# in32.net
KiCad netlist of a schematic drawn in EAGLE
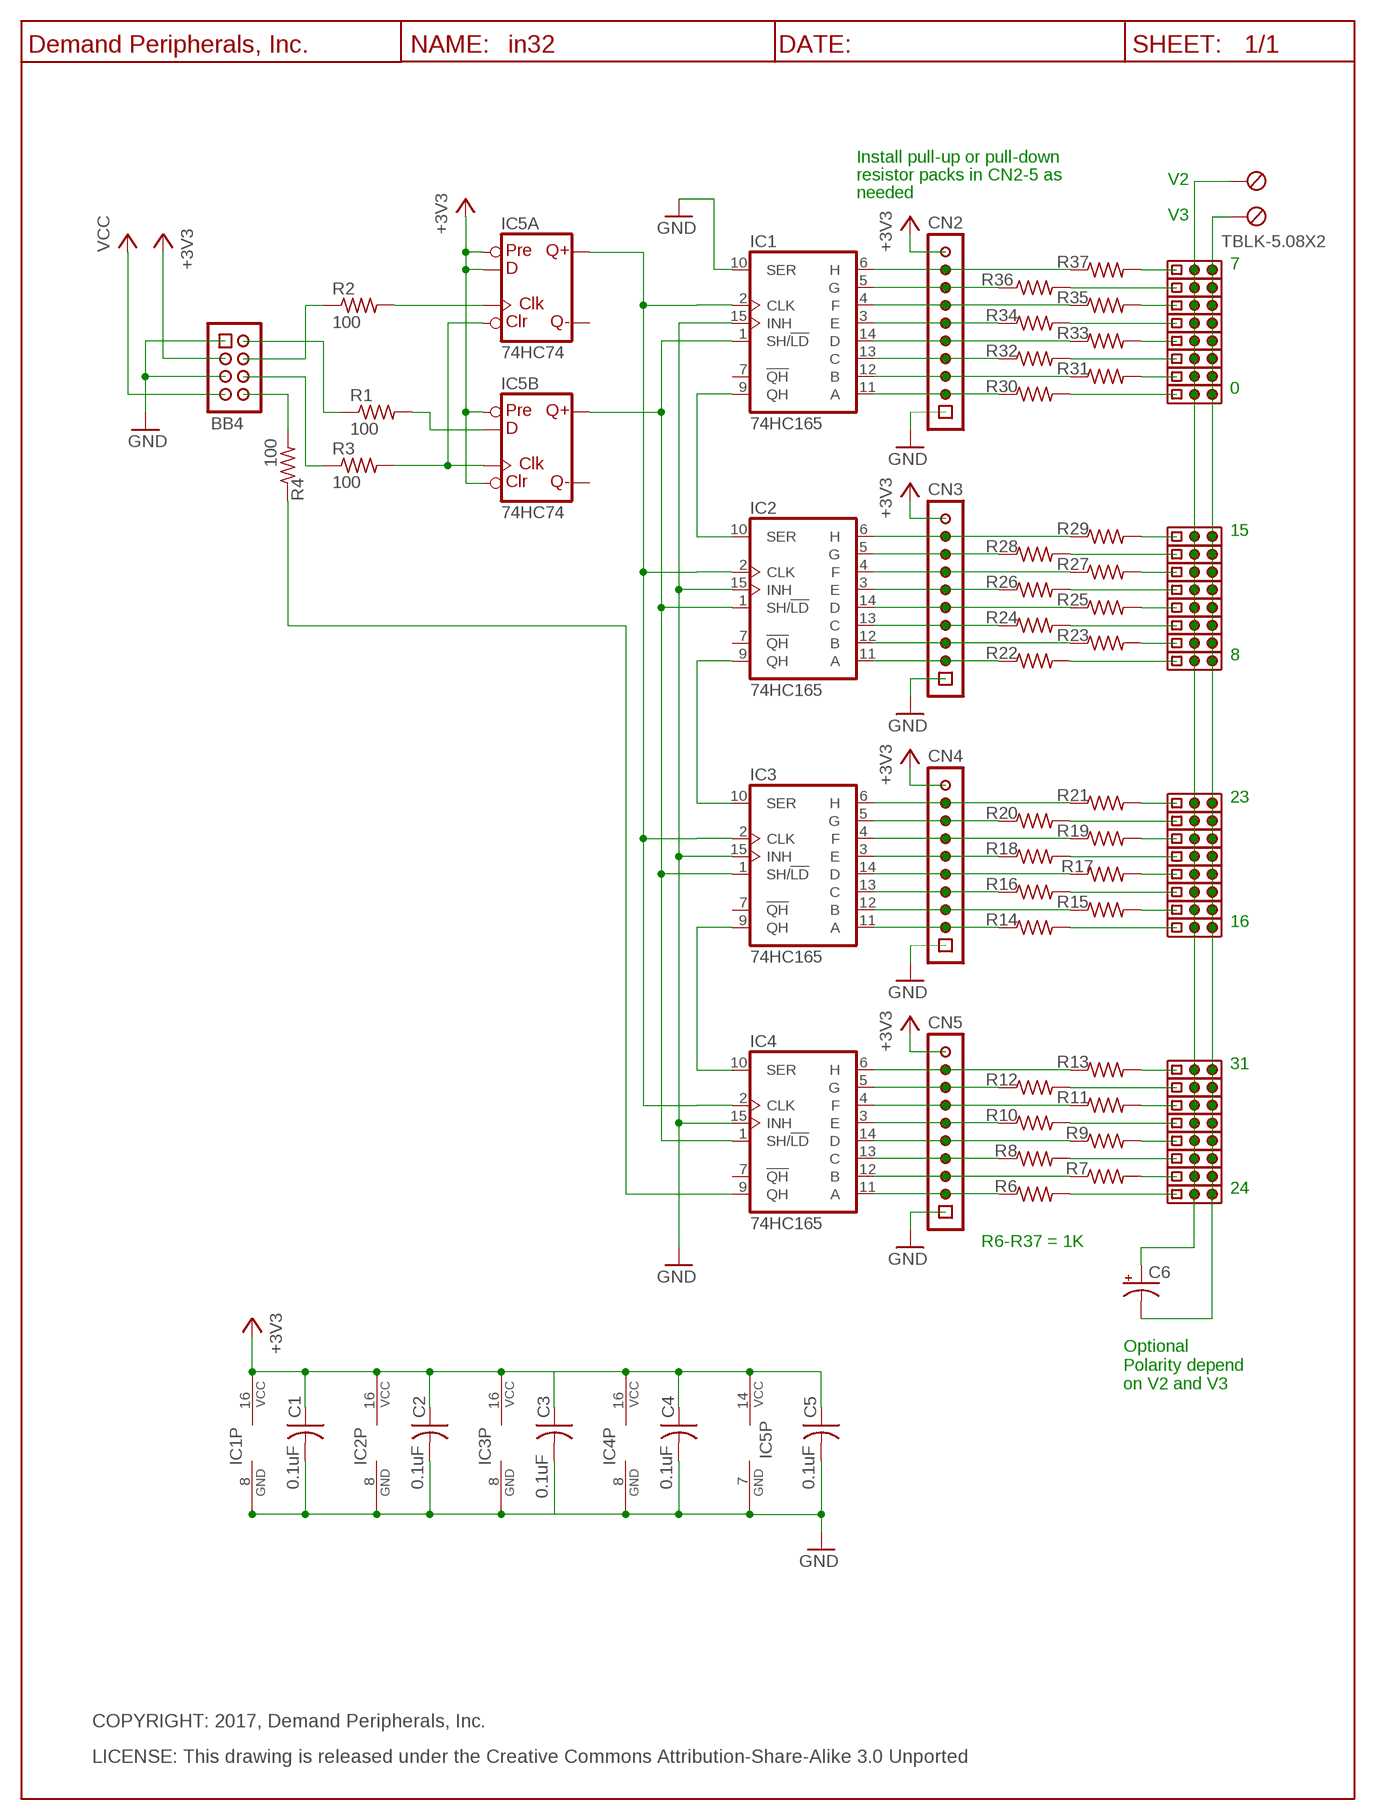
[diagram p0: schematic, sheet 1]

(export (version "E")
  (design (tool "Eeschema 10.0.6"))
  (components
    (comp (ref "BB4")
      (value "Keyed_Pin_Header_4x2(0.1\"x0.1\")")
      (footprint "eagle-import:HDR-4X2")
      (libsource (lib "eagle-import") (part "HDR-4X2-SHR"))
    )
    (comp (ref "C1")
      (value "0.1uF")
      (footprint "eagle-import:C0603")
      (libsource (lib "eagle-import") (part "C0.1UF_C0603"))
    )
    (comp (ref "C2")
      (value "0.1uF")
      (footprint "eagle-import:C0603")
      (libsource (lib "eagle-import") (part "C0.1UF_C0603"))
    )
    (comp (ref "C3")
      (value "0.1uF")
      (footprint "eagle-import:C0603")
      (libsource (lib "eagle-import") (part "C0.1UF_C0603"))
    )
    (comp (ref "C4")
      (value "0.1uF")
      (footprint "eagle-import:C0603")
      (libsource (lib "eagle-import") (part "C0.1UF_C0603"))
    )
    (comp (ref "C5")
      (value "0.1uF")
      (footprint "eagle-import:C0603")
      (libsource (lib "eagle-import") (part "C0.1UF_C0603"))
    )
    (comp (ref "C6")
      (value "C100UF_E3.5-10")
      (footprint "eagle-import:E3.5-10")
      (libsource (lib "eagle-import") (part "C100UF_E3.5-10"))
    )
    (comp (ref "CN1")
      (value "TBLK-5.08X2")
      (footprint "eagle-import:TBLK-5.08-X2")
      (libsource (lib "eagle-import") (part "TBLK-5.08-X2"))
    )
    (comp (ref "CN2")
      (value "HDR-10X1")
      (footprint "eagle-import:HDR-10X1")
      (libsource (lib "eagle-import") (part "HDR-10X1"))
    )
    (comp (ref "CN3")
      (value "HDR-10X1")
      (footprint "eagle-import:HDR-10X1")
      (libsource (lib "eagle-import") (part "HDR-10X1"))
    )
    (comp (ref "CN4")
      (value "HDR-10X1")
      (footprint "eagle-import:HDR-10X1")
      (libsource (lib "eagle-import") (part "HDR-10X1"))
    )
    (comp (ref "CN5")
      (value "HDR-10X1")
      (footprint "eagle-import:HDR-10X1")
      (libsource (lib "eagle-import") (part "HDR-10X1"))
    )
    (comp (ref "IC1")
      (value "74HC165")
      (footprint "eagle-import:SO16")
      (libsource (lib "eagle-import") (part "74HC165"))
    )
    (comp (ref "IC2")
      (value "74HC165")
      (footprint "eagle-import:SO16")
      (libsource (lib "eagle-import") (part "74HC165"))
    )
    (comp (ref "IC3")
      (value "74HC165")
      (footprint "eagle-import:SO16")
      (libsource (lib "eagle-import") (part "74HC165"))
    )
    (comp (ref "IC4")
      (value "74HC165")
      (footprint "eagle-import:SO16")
      (libsource (lib "eagle-import") (part "74HC165"))
    )
    (comp (ref "IC5")
      (value "74HC74")
      (footprint "eagle-import:SO14")
      (libsource (lib "eagle-import") (part "74AHC74"))
    )
    (comp (ref "R1")
      (value "100")
      (footprint "eagle-import:R0603")
      (libsource (lib "eagle-import") (part "R100_R0603"))
    )
    (comp (ref "R2")
      (value "100")
      (footprint "eagle-import:R0603")
      (libsource (lib "eagle-import") (part "R100_R0603"))
    )
    (comp (ref "R3")
      (value "100")
      (footprint "eagle-import:R0603")
      (libsource (lib "eagle-import") (part "R100_R0603"))
    )
    (comp (ref "R4")
      (value "100")
      (footprint "eagle-import:R0603")
      (libsource (lib "eagle-import") (part "R100_R0603"))
    )
    (comp (ref "R6")
      (value "R1K_R0603")
      (footprint "eagle-import:R0603")
      (libsource (lib "eagle-import") (part "R1K_R0603"))
    )
    (comp (ref "R7")
      (value "R1K_R0603")
      (footprint "eagle-import:R0603")
      (libsource (lib "eagle-import") (part "R1K_R0603"))
    )
    (comp (ref "R8")
      (value "R1K_R0603")
      (footprint "eagle-import:R0603")
      (libsource (lib "eagle-import") (part "R1K_R0603"))
    )
    (comp (ref "R9")
      (value "R1K_R0603")
      (footprint "eagle-import:R0603")
      (libsource (lib "eagle-import") (part "R1K_R0603"))
    )
    (comp (ref "R10")
      (value "R1K_R0603")
      (footprint "eagle-import:R0603")
      (libsource (lib "eagle-import") (part "R1K_R0603"))
    )
    (comp (ref "R11")
      (value "R1K_R0603")
      (footprint "eagle-import:R0603")
      (libsource (lib "eagle-import") (part "R1K_R0603"))
    )
    (comp (ref "R12")
      (value "R1K_R0603")
      (footprint "eagle-import:R0603")
      (libsource (lib "eagle-import") (part "R1K_R0603"))
    )
    (comp (ref "R13")
      (value "R1K_R0603")
      (footprint "eagle-import:R0603")
      (libsource (lib "eagle-import") (part "R1K_R0603"))
    )
    (comp (ref "R14")
      (value "R1K_R0603")
      (footprint "eagle-import:R0603")
      (libsource (lib "eagle-import") (part "R1K_R0603"))
    )
    (comp (ref "R15")
      (value "R1K_R0603")
      (footprint "eagle-import:R0603")
      (libsource (lib "eagle-import") (part "R1K_R0603"))
    )
    (comp (ref "R16")
      (value "R1K_R0603")
      (footprint "eagle-import:R0603")
      (libsource (lib "eagle-import") (part "R1K_R0603"))
    )
    (comp (ref "R17")
      (value "R1K_R0603")
      (footprint "eagle-import:R0603")
      (libsource (lib "eagle-import") (part "R1K_R0603"))
    )
    (comp (ref "R18")
      (value "R1K_R0603")
      (footprint "eagle-import:R0603")
      (libsource (lib "eagle-import") (part "R1K_R0603"))
    )
    (comp (ref "R19")
      (value "R1K_R0603")
      (footprint "eagle-import:R0603")
      (libsource (lib "eagle-import") (part "R1K_R0603"))
    )
    (comp (ref "R20")
      (value "R1K_R0603")
      (footprint "eagle-import:R0603")
      (libsource (lib "eagle-import") (part "R1K_R0603"))
    )
    (comp (ref "R21")
      (value "R1K_R0603")
      (footprint "eagle-import:R0603")
      (libsource (lib "eagle-import") (part "R1K_R0603"))
    )
    (comp (ref "R22")
      (value "R1K_R0603")
      (footprint "eagle-import:R0603")
      (libsource (lib "eagle-import") (part "R1K_R0603"))
    )
    (comp (ref "R23")
      (value "R1K_R0603")
      (footprint "eagle-import:R0603")
      (libsource (lib "eagle-import") (part "R1K_R0603"))
    )
    (comp (ref "R24")
      (value "R1K_R0603")
      (footprint "eagle-import:R0603")
      (libsource (lib "eagle-import") (part "R1K_R0603"))
    )
    (comp (ref "R25")
      (value "R1K_R0603")
      (footprint "eagle-import:R0603")
      (libsource (lib "eagle-import") (part "R1K_R0603"))
    )
    (comp (ref "R26")
      (value "R1K_R0603")
      (footprint "eagle-import:R0603")
      (libsource (lib "eagle-import") (part "R1K_R0603"))
    )
    (comp (ref "R27")
      (value "R1K_R0603")
      (footprint "eagle-import:R0603")
      (libsource (lib "eagle-import") (part "R1K_R0603"))
    )
    (comp (ref "R28")
      (value "R1K_R0603")
      (footprint "eagle-import:R0603")
      (libsource (lib "eagle-import") (part "R1K_R0603"))
    )
    (comp (ref "R29")
      (value "R1K_R0603")
      (footprint "eagle-import:R0603")
      (libsource (lib "eagle-import") (part "R1K_R0603"))
    )
    (comp (ref "R30")
      (value "R1K_R0603")
      (footprint "eagle-import:R0603")
      (libsource (lib "eagle-import") (part "R1K_R0603"))
    )
    (comp (ref "R31")
      (value "R1K_R0603")
      (footprint "eagle-import:R0603")
      (libsource (lib "eagle-import") (part "R1K_R0603"))
    )
    (comp (ref "R32")
      (value "R1K_R0603")
      (footprint "eagle-import:R0603")
      (libsource (lib "eagle-import") (part "R1K_R0603"))
    )
    (comp (ref "R33")
      (value "R1K_R0603")
      (footprint "eagle-import:R0603")
      (libsource (lib "eagle-import") (part "R1K_R0603"))
    )
    (comp (ref "R34")
      (value "R1K_R0603")
      (footprint "eagle-import:R0603")
      (libsource (lib "eagle-import") (part "R1K_R0603"))
    )
    (comp (ref "R35")
      (value "R1K_R0603")
      (footprint "eagle-import:R0603")
      (libsource (lib "eagle-import") (part "R1K_R0603"))
    )
    (comp (ref "R36")
      (value "R1K_R0603")
      (footprint "eagle-import:R0603")
      (libsource (lib "eagle-import") (part "R1K_R0603"))
    )
    (comp (ref "R37")
      (value "R1K_R0603")
      (footprint "eagle-import:R0603")
      (libsource (lib "eagle-import") (part "R1K_R0603"))
    )
    (comp (ref "U$2")
      (value "DP_FRAME_P")
      (footprint "eagle-import:P_FRAME")
      (libsource (lib "eagle-import") (part "DP_FRAME_P"))
    )
    (comp (ref "U$8")
      (value "HDR-3X1")
      (footprint "eagle-import:HDR-3X1")
      (libsource (lib "eagle-import") (part "HDR-3X1"))
    )
    (comp (ref "U$9")
      (value "HDR-3X1")
      (footprint "eagle-import:HDR-3X1")
      (libsource (lib "eagle-import") (part "HDR-3X1"))
    )
    (comp (ref "U$10")
      (value "HDR-3X1")
      (footprint "eagle-import:HDR-3X1")
      (libsource (lib "eagle-import") (part "HDR-3X1"))
    )
    (comp (ref "U$11")
      (value "HDR-3X1")
      (footprint "eagle-import:HDR-3X1")
      (libsource (lib "eagle-import") (part "HDR-3X1"))
    )
    (comp (ref "U$12")
      (value "HDR-3X1")
      (footprint "eagle-import:HDR-3X1")
      (libsource (lib "eagle-import") (part "HDR-3X1"))
    )
    (comp (ref "U$13")
      (value "HDR-3X1")
      (footprint "eagle-import:HDR-3X1")
      (libsource (lib "eagle-import") (part "HDR-3X1"))
    )
    (comp (ref "U$14")
      (value "HDR-3X1")
      (footprint "eagle-import:HDR-3X1")
      (libsource (lib "eagle-import") (part "HDR-3X1"))
    )
    (comp (ref "U$15")
      (value "HDR-3X1")
      (footprint "eagle-import:HDR-3X1")
      (libsource (lib "eagle-import") (part "HDR-3X1"))
    )
    (comp (ref "U$16")
      (value "HDR-3X1")
      (footprint "eagle-import:HDR-3X1")
      (libsource (lib "eagle-import") (part "HDR-3X1"))
    )
    (comp (ref "U$17")
      (value "HDR-3X1")
      (footprint "eagle-import:HDR-3X1")
      (libsource (lib "eagle-import") (part "HDR-3X1"))
    )
    (comp (ref "U$18")
      (value "HDR-3X1")
      (footprint "eagle-import:HDR-3X1")
      (libsource (lib "eagle-import") (part "HDR-3X1"))
    )
    (comp (ref "U$19")
      (value "HDR-3X1")
      (footprint "eagle-import:HDR-3X1")
      (libsource (lib "eagle-import") (part "HDR-3X1"))
    )
    (comp (ref "U$20")
      (value "HDR-3X1")
      (footprint "eagle-import:HDR-3X1")
      (libsource (lib "eagle-import") (part "HDR-3X1"))
    )
    (comp (ref "U$21")
      (value "HDR-3X1")
      (footprint "eagle-import:HDR-3X1")
      (libsource (lib "eagle-import") (part "HDR-3X1"))
    )
    (comp (ref "U$22")
      (value "HDR-3X1")
      (footprint "eagle-import:HDR-3X1")
      (libsource (lib "eagle-import") (part "HDR-3X1"))
    )
    (comp (ref "U$23")
      (value "HDR-3X1")
      (footprint "eagle-import:HDR-3X1")
      (libsource (lib "eagle-import") (part "HDR-3X1"))
    )
    (comp (ref "U$24")
      (value "HDR-3X1")
      (footprint "eagle-import:HDR-3X1")
      (libsource (lib "eagle-import") (part "HDR-3X1"))
    )
    (comp (ref "U$25")
      (value "HDR-3X1")
      (footprint "eagle-import:HDR-3X1")
      (libsource (lib "eagle-import") (part "HDR-3X1"))
    )
    (comp (ref "U$26")
      (value "HDR-3X1")
      (footprint "eagle-import:HDR-3X1")
      (libsource (lib "eagle-import") (part "HDR-3X1"))
    )
    (comp (ref "U$27")
      (value "HDR-3X1")
      (footprint "eagle-import:HDR-3X1")
      (libsource (lib "eagle-import") (part "HDR-3X1"))
    )
    (comp (ref "U$28")
      (value "HDR-3X1")
      (footprint "eagle-import:HDR-3X1")
      (libsource (lib "eagle-import") (part "HDR-3X1"))
    )
    (comp (ref "U$29")
      (value "HDR-3X1")
      (footprint "eagle-import:HDR-3X1")
      (libsource (lib "eagle-import") (part "HDR-3X1"))
    )
    (comp (ref "U$30")
      (value "HDR-3X1")
      (footprint "eagle-import:HDR-3X1")
      (libsource (lib "eagle-import") (part "HDR-3X1"))
    )
    (comp (ref "U$31")
      (value "HDR-3X1")
      (footprint "eagle-import:HDR-3X1")
      (libsource (lib "eagle-import") (part "HDR-3X1"))
    )
    (comp (ref "U$32")
      (value "HDR-3X1")
      (footprint "eagle-import:HDR-3X1")
      (libsource (lib "eagle-import") (part "HDR-3X1"))
    )
    (comp (ref "U$33")
      (value "HDR-3X1")
      (footprint "eagle-import:HDR-3X1")
      (libsource (lib "eagle-import") (part "HDR-3X1"))
    )
    (comp (ref "U$34")
      (value "HDR-3X1")
      (footprint "eagle-import:HDR-3X1")
      (libsource (lib "eagle-import") (part "HDR-3X1"))
    )
    (comp (ref "U$35")
      (value "HDR-3X1")
      (footprint "eagle-import:HDR-3X1")
      (libsource (lib "eagle-import") (part "HDR-3X1"))
    )
    (comp (ref "U$36")
      (value "HDR-3X1")
      (footprint "eagle-import:HDR-3X1")
      (libsource (lib "eagle-import") (part "HDR-3X1"))
    )
    (comp (ref "U$37")
      (value "HDR-3X1")
      (footprint "eagle-import:HDR-3X1")
      (libsource (lib "eagle-import") (part "HDR-3X1"))
    )
    (comp (ref "U$38")
      (value "HDR-3X1")
      (footprint "eagle-import:HDR-3X1")
      (libsource (lib "eagle-import") (part "HDR-3X1"))
    )
    (comp (ref "U$39")
      (value "HDR-3X1")
      (footprint "eagle-import:HDR-3X1")
      (libsource (lib "eagle-import") (part "HDR-3X1"))
    )
  )
  (nets
    (net (code "1") (name "+3V3") (class "Default")
      (node (ref "BB4") (pin "3") (pinfunction "3_3") (pintype "passive"))
      (node (ref "C1") (pin "1") (pinfunction "1_1") (pintype "passive"))
      (node (ref "C2") (pin "1") (pinfunction "1_1") (pintype "passive"))
      (node (ref "C3") (pin "1") (pinfunction "1_1") (pintype "passive"))
      (node (ref "C4") (pin "1") (pinfunction "1_1") (pintype "passive"))
      (node (ref "C5") (pin "1") (pinfunction "1_1") (pintype "passive"))
      (node (ref "CN2") (pin "10") (pinfunction "10_10") (pintype "passive"))
      (node (ref "CN3") (pin "10") (pinfunction "10_10") (pintype "passive"))
      (node (ref "CN4") (pin "10") (pinfunction "10_10") (pintype "passive"))
      (node (ref "CN5") (pin "10") (pinfunction "10_10") (pintype "passive"))
      (node (ref "IC1") (pin "16") (pinfunction "VCC_16") (pintype "power_in"))
      (node (ref "IC2") (pin "16") (pinfunction "VCC_16") (pintype "power_in"))
      (node (ref "IC3") (pin "16") (pinfunction "VCC_16") (pintype "power_in"))
      (node (ref "IC4") (pin "16") (pinfunction "VCC_16") (pintype "power_in"))
      (node (ref "IC5") (pin "10") (pinfunction "PRE_10") (pintype "input"))
      (node (ref "IC5") (pin "13") (pinfunction "CLR_13") (pintype "input"))
      (node (ref "IC5") (pin "14") (pinfunction "VCC_14") (pintype "power_in"))
      (node (ref "IC5") (pin "2") (pinfunction "D_2") (pintype "input"))
      (node (ref "IC5") (pin "4") (pinfunction "PRE_4") (pintype "input"))
    )
    (net (code "2") (name "GND") (class "Default")
      (node (ref "BB4") (pin "1") (pinfunction "1_1") (pintype "passive"))
      (node (ref "BB4") (pin "5") (pinfunction "5_5") (pintype "passive"))
      (node (ref "C1") (pin "2") (pinfunction "2_2") (pintype "passive"))
      (node (ref "C2") (pin "2") (pinfunction "2_2") (pintype "passive"))
      (node (ref "C3") (pin "2") (pinfunction "2_2") (pintype "passive"))
      (node (ref "C4") (pin "2") (pinfunction "2_2") (pintype "passive"))
      (node (ref "C5") (pin "2") (pinfunction "2_2") (pintype "passive"))
      (node (ref "CN2") (pin "1") (pinfunction "1_1") (pintype "passive"))
      (node (ref "CN3") (pin "1") (pinfunction "1_1") (pintype "passive"))
      (node (ref "CN4") (pin "1") (pinfunction "1_1") (pintype "passive"))
      (node (ref "CN5") (pin "1") (pinfunction "1_1") (pintype "passive"))
      (node (ref "IC1") (pin "10") (pinfunction "SER_10") (pintype "input"))
      (node (ref "IC1") (pin "15") (pinfunction "INH_15") (pintype "input"))
      (node (ref "IC1") (pin "8") (pinfunction "GND_8") (pintype "power_in"))
      (node (ref "IC2") (pin "15") (pinfunction "INH_15") (pintype "input"))
      (node (ref "IC2") (pin "8") (pinfunction "GND_8") (pintype "power_in"))
      (node (ref "IC3") (pin "15") (pinfunction "INH_15") (pintype "input"))
      (node (ref "IC3") (pin "8") (pinfunction "GND_8") (pintype "power_in"))
      (node (ref "IC4") (pin "15") (pinfunction "INH_15") (pintype "input"))
      (node (ref "IC4") (pin "8") (pinfunction "GND_8") (pintype "power_in"))
      (node (ref "IC5") (pin "7") (pinfunction "GND_7") (pintype "power_in"))
    )
    (net (code "3") (name "Net-(BB4-Pad2)") (class "Default")
      (node (ref "BB4") (pin "2") (pinfunction "2_2") (pintype "passive"))
      (node (ref "R1") (pin "1") (pinfunction "1_1") (pintype "passive"))
    )
    (net (code "4") (name "Net-(BB4-Pad4)") (class "Default")
      (node (ref "BB4") (pin "4") (pinfunction "4_4") (pintype "passive"))
      (node (ref "R2") (pin "1") (pinfunction "1_1") (pintype "passive"))
    )
    (net (code "5") (name "Net-(BB4-Pad6)") (class "Default")
      (node (ref "BB4") (pin "6") (pinfunction "6_6") (pintype "passive"))
      (node (ref "R3") (pin "1") (pinfunction "1_1") (pintype "passive"))
    )
    (net (code "6") (name "Net-(BB4-Pad8)") (class "Default")
      (node (ref "BB4") (pin "8") (pinfunction "8_8") (pintype "passive"))
      (node (ref "R4") (pin "2") (pinfunction "2_2") (pintype "passive"))
    )
    (net (code "7") (name "Net-(CN1-KL)") (class "Default")
      (node (ref "C6") (pin "+") (pinfunction "+_+") (pintype "passive"))
      (node (ref "CN1") (pin "1") (pinfunction "KL_1") (pintype "passive"))
      (node (ref "U$10") (pin "2") (pinfunction "2_2") (pintype "passive"))
      (node (ref "U$11") (pin "2") (pinfunction "2_2") (pintype "passive"))
      (node (ref "U$12") (pin "2") (pinfunction "2_2") (pintype "passive"))
      (node (ref "U$13") (pin "2") (pinfunction "2_2") (pintype "passive"))
      (node (ref "U$14") (pin "2") (pinfunction "2_2") (pintype "passive"))
      (node (ref "U$15") (pin "2") (pinfunction "2_2") (pintype "passive"))
      (node (ref "U$16") (pin "2") (pinfunction "2_2") (pintype "passive"))
      (node (ref "U$17") (pin "2") (pinfunction "2_2") (pintype "passive"))
      (node (ref "U$18") (pin "2") (pinfunction "2_2") (pintype "passive"))
      (node (ref "U$19") (pin "2") (pinfunction "2_2") (pintype "passive"))
      (node (ref "U$20") (pin "2") (pinfunction "2_2") (pintype "passive"))
      (node (ref "U$21") (pin "2") (pinfunction "2_2") (pintype "passive"))
      (node (ref "U$22") (pin "2") (pinfunction "2_2") (pintype "passive"))
      (node (ref "U$23") (pin "2") (pinfunction "2_2") (pintype "passive"))
      (node (ref "U$24") (pin "2") (pinfunction "2_2") (pintype "passive"))
      (node (ref "U$25") (pin "2") (pinfunction "2_2") (pintype "passive"))
      (node (ref "U$26") (pin "2") (pinfunction "2_2") (pintype "passive"))
      (node (ref "U$27") (pin "2") (pinfunction "2_2") (pintype "passive"))
      (node (ref "U$28") (pin "2") (pinfunction "2_2") (pintype "passive"))
      (node (ref "U$29") (pin "2") (pinfunction "2_2") (pintype "passive"))
      (node (ref "U$30") (pin "2") (pinfunction "2_2") (pintype "passive"))
      (node (ref "U$31") (pin "2") (pinfunction "2_2") (pintype "passive"))
      (node (ref "U$32") (pin "2") (pinfunction "2_2") (pintype "passive"))
      (node (ref "U$33") (pin "2") (pinfunction "2_2") (pintype "passive"))
      (node (ref "U$34") (pin "2") (pinfunction "2_2") (pintype "passive"))
      (node (ref "U$35") (pin "2") (pinfunction "2_2") (pintype "passive"))
      (node (ref "U$36") (pin "2") (pinfunction "2_2") (pintype "passive"))
      (node (ref "U$37") (pin "2") (pinfunction "2_2") (pintype "passive"))
      (node (ref "U$38") (pin "2") (pinfunction "2_2") (pintype "passive"))
      (node (ref "U$39") (pin "2") (pinfunction "2_2") (pintype "passive"))
      (node (ref "U$8") (pin "2") (pinfunction "2_2") (pintype "passive"))
      (node (ref "U$9") (pin "2") (pinfunction "2_2") (pintype "passive"))
    )
    (net (code "8") (name "Net-(CN1-KL1)") (class "Default")
      (node (ref "C6") (pin "-") (pinfunction "-_-") (pintype "passive"))
      (node (ref "CN1") (pin "2") (pinfunction "KL1_2") (pintype "passive"))
      (node (ref "U$10") (pin "3") (pinfunction "3_3") (pintype "passive"))
      (node (ref "U$11") (pin "3") (pinfunction "3_3") (pintype "passive"))
      (node (ref "U$12") (pin "3") (pinfunction "3_3") (pintype "passive"))
      (node (ref "U$13") (pin "3") (pinfunction "3_3") (pintype "passive"))
      (node (ref "U$14") (pin "3") (pinfunction "3_3") (pintype "passive"))
      (node (ref "U$15") (pin "3") (pinfunction "3_3") (pintype "passive"))
      (node (ref "U$16") (pin "3") (pinfunction "3_3") (pintype "passive"))
      (node (ref "U$17") (pin "3") (pinfunction "3_3") (pintype "passive"))
      (node (ref "U$18") (pin "3") (pinfunction "3_3") (pintype "passive"))
      (node (ref "U$19") (pin "3") (pinfunction "3_3") (pintype "passive"))
      (node (ref "U$20") (pin "3") (pinfunction "3_3") (pintype "passive"))
      (node (ref "U$21") (pin "3") (pinfunction "3_3") (pintype "passive"))
      (node (ref "U$22") (pin "3") (pinfunction "3_3") (pintype "passive"))
      (node (ref "U$23") (pin "3") (pinfunction "3_3") (pintype "passive"))
      (node (ref "U$24") (pin "3") (pinfunction "3_3") (pintype "passive"))
      (node (ref "U$25") (pin "3") (pinfunction "3_3") (pintype "passive"))
      (node (ref "U$26") (pin "3") (pinfunction "3_3") (pintype "passive"))
      (node (ref "U$27") (pin "3") (pinfunction "3_3") (pintype "passive"))
      (node (ref "U$28") (pin "3") (pinfunction "3_3") (pintype "passive"))
      (node (ref "U$29") (pin "3") (pinfunction "3_3") (pintype "passive"))
      (node (ref "U$30") (pin "3") (pinfunction "3_3") (pintype "passive"))
      (node (ref "U$31") (pin "3") (pinfunction "3_3") (pintype "passive"))
      (node (ref "U$32") (pin "3") (pinfunction "3_3") (pintype "passive"))
      (node (ref "U$33") (pin "3") (pinfunction "3_3") (pintype "passive"))
      (node (ref "U$34") (pin "3") (pinfunction "3_3") (pintype "passive"))
      (node (ref "U$35") (pin "3") (pinfunction "3_3") (pintype "passive"))
      (node (ref "U$36") (pin "3") (pinfunction "3_3") (pintype "passive"))
      (node (ref "U$37") (pin "3") (pinfunction "3_3") (pintype "passive"))
      (node (ref "U$38") (pin "3") (pinfunction "3_3") (pintype "passive"))
      (node (ref "U$39") (pin "3") (pinfunction "3_3") (pintype "passive"))
      (node (ref "U$8") (pin "3") (pinfunction "3_3") (pintype "passive"))
      (node (ref "U$9") (pin "3") (pinfunction "3_3") (pintype "passive"))
    )
    (net (code "9") (name "Net-(IC1A-A)") (class "Default")
      (node (ref "CN2") (pin "2") (pinfunction "2_2") (pintype "passive"))
      (node (ref "IC1") (pin "11") (pinfunction "A_11") (pintype "input"))
      (node (ref "R30") (pin "1") (pinfunction "1_1") (pintype "passive"))
    )
    (net (code "10") (name "Net-(IC1A-B)") (class "Default")
      (node (ref "CN2") (pin "3") (pinfunction "3_3") (pintype "passive"))
      (node (ref "IC1") (pin "12") (pinfunction "B_12") (pintype "input"))
      (node (ref "R31") (pin "1") (pinfunction "1_1") (pintype "passive"))
    )
    (net (code "11") (name "Net-(IC1A-C)") (class "Default")
      (node (ref "CN2") (pin "4") (pinfunction "4_4") (pintype "passive"))
      (node (ref "IC1") (pin "13") (pinfunction "C_13") (pintype "input"))
      (node (ref "R32") (pin "1") (pinfunction "1_1") (pintype "passive"))
    )
    (net (code "12") (name "Net-(IC1A-CLK)") (class "Default")
      (node (ref "IC1") (pin "2") (pinfunction "CLK_2") (pintype "input"))
      (node (ref "IC2") (pin "2") (pinfunction "CLK_2") (pintype "input"))
      (node (ref "IC3") (pin "2") (pinfunction "CLK_2") (pintype "input"))
      (node (ref "IC4") (pin "2") (pinfunction "CLK_2") (pintype "input"))
      (node (ref "IC5") (pin "5") (pinfunction "Q_5") (pintype "output"))
    )
    (net (code "13") (name "Net-(IC1A-D)") (class "Default")
      (node (ref "CN2") (pin "5") (pinfunction "5_5") (pintype "passive"))
      (node (ref "IC1") (pin "14") (pinfunction "D_14") (pintype "input"))
      (node (ref "R33") (pin "1") (pinfunction "1_1") (pintype "passive"))
    )
    (net (code "14") (name "Net-(IC1A-E)") (class "Default")
      (node (ref "CN2") (pin "6") (pinfunction "6_6") (pintype "passive"))
      (node (ref "IC1") (pin "3") (pinfunction "E_3") (pintype "input"))
      (node (ref "R34") (pin "1") (pinfunction "1_1") (pintype "passive"))
    )
    (net (code "15") (name "Net-(IC1A-F)") (class "Default")
      (node (ref "CN2") (pin "7") (pinfunction "7_7") (pintype "passive"))
      (node (ref "IC1") (pin "4") (pinfunction "F_4") (pintype "input"))
      (node (ref "R35") (pin "1") (pinfunction "1_1") (pintype "passive"))
    )
    (net (code "16") (name "Net-(IC1A-G)") (class "Default")
      (node (ref "CN2") (pin "8") (pinfunction "8_8") (pintype "passive"))
      (node (ref "IC1") (pin "5") (pinfunction "G_5") (pintype "input"))
      (node (ref "R36") (pin "1") (pinfunction "1_1") (pintype "passive"))
    )
    (net (code "17") (name "Net-(IC1A-H)") (class "Default")
      (node (ref "CN2") (pin "9") (pinfunction "9_9") (pintype "passive"))
      (node (ref "IC1") (pin "6") (pinfunction "H_6") (pintype "input"))
      (node (ref "R37") (pin "1") (pinfunction "1_1") (pintype "passive"))
    )
    (net (code "18") (name "Net-(IC1A-QH)") (class "Default")
      (node (ref "IC1") (pin "9") (pinfunction "QH_9") (pintype "output"))
      (node (ref "IC2") (pin "10") (pinfunction "SER_10") (pintype "input"))
    )
    (net (code "19") (name "Net-(IC1A-SH{slash}~{LD})") (class "Default")
      (node (ref "IC1") (pin "1") (pinfunction "SH/~{LD}_1") (pintype "input"))
      (node (ref "IC2") (pin "1") (pinfunction "SH/~{LD}_1") (pintype "input"))
      (node (ref "IC3") (pin "1") (pinfunction "SH/~{LD}_1") (pintype "input"))
      (node (ref "IC4") (pin "1") (pinfunction "SH/~{LD}_1") (pintype "input"))
      (node (ref "IC5") (pin "9") (pinfunction "Q_9") (pintype "output"))
    )
    (net (code "20") (name "Net-(IC2A-A)") (class "Default")
      (node (ref "CN3") (pin "2") (pinfunction "2_2") (pintype "passive"))
      (node (ref "IC2") (pin "11") (pinfunction "A_11") (pintype "input"))
      (node (ref "R22") (pin "1") (pinfunction "1_1") (pintype "passive"))
    )
    (net (code "21") (name "Net-(IC2A-B)") (class "Default")
      (node (ref "CN3") (pin "3") (pinfunction "3_3") (pintype "passive"))
      (node (ref "IC2") (pin "12") (pinfunction "B_12") (pintype "input"))
      (node (ref "R23") (pin "1") (pinfunction "1_1") (pintype "passive"))
    )
    (net (code "22") (name "Net-(IC2A-C)") (class "Default")
      (node (ref "CN3") (pin "4") (pinfunction "4_4") (pintype "passive"))
      (node (ref "IC2") (pin "13") (pinfunction "C_13") (pintype "input"))
      (node (ref "R24") (pin "1") (pinfunction "1_1") (pintype "passive"))
    )
    (net (code "23") (name "Net-(IC2A-D)") (class "Default")
      (node (ref "CN3") (pin "5") (pinfunction "5_5") (pintype "passive"))
      (node (ref "IC2") (pin "14") (pinfunction "D_14") (pintype "input"))
      (node (ref "R25") (pin "1") (pinfunction "1_1") (pintype "passive"))
    )
    (net (code "24") (name "Net-(IC2A-E)") (class "Default")
      (node (ref "CN3") (pin "6") (pinfunction "6_6") (pintype "passive"))
      (node (ref "IC2") (pin "3") (pinfunction "E_3") (pintype "input"))
      (node (ref "R26") (pin "1") (pinfunction "1_1") (pintype "passive"))
    )
    (net (code "25") (name "Net-(IC2A-F)") (class "Default")
      (node (ref "CN3") (pin "7") (pinfunction "7_7") (pintype "passive"))
      (node (ref "IC2") (pin "4") (pinfunction "F_4") (pintype "input"))
      (node (ref "R27") (pin "1") (pinfunction "1_1") (pintype "passive"))
    )
    (net (code "26") (name "Net-(IC2A-G)") (class "Default")
      (node (ref "CN3") (pin "8") (pinfunction "8_8") (pintype "passive"))
      (node (ref "IC2") (pin "5") (pinfunction "G_5") (pintype "input"))
      (node (ref "R28") (pin "1") (pinfunction "1_1") (pintype "passive"))
    )
    (net (code "27") (name "Net-(IC2A-H)") (class "Default")
      (node (ref "CN3") (pin "9") (pinfunction "9_9") (pintype "passive"))
      (node (ref "IC2") (pin "6") (pinfunction "H_6") (pintype "input"))
      (node (ref "R29") (pin "1") (pinfunction "1_1") (pintype "passive"))
    )
    (net (code "28") (name "Net-(IC2A-QH)") (class "Default")
      (node (ref "IC2") (pin "9") (pinfunction "QH_9") (pintype "output"))
      (node (ref "IC3") (pin "10") (pinfunction "SER_10") (pintype "input"))
    )
    (net (code "29") (name "Net-(IC3A-A)") (class "Default")
      (node (ref "CN4") (pin "2") (pinfunction "2_2") (pintype "passive"))
      (node (ref "IC3") (pin "11") (pinfunction "A_11") (pintype "input"))
      (node (ref "R14") (pin "1") (pinfunction "1_1") (pintype "passive"))
    )
    (net (code "30") (name "Net-(IC3A-B)") (class "Default")
      (node (ref "CN4") (pin "3") (pinfunction "3_3") (pintype "passive"))
      (node (ref "IC3") (pin "12") (pinfunction "B_12") (pintype "input"))
      (node (ref "R15") (pin "1") (pinfunction "1_1") (pintype "passive"))
    )
    (net (code "31") (name "Net-(IC3A-C)") (class "Default")
      (node (ref "CN4") (pin "4") (pinfunction "4_4") (pintype "passive"))
      (node (ref "IC3") (pin "13") (pinfunction "C_13") (pintype "input"))
      (node (ref "R16") (pin "1") (pinfunction "1_1") (pintype "passive"))
    )
    (net (code "32") (name "Net-(IC3A-D)") (class "Default")
      (node (ref "CN4") (pin "5") (pinfunction "5_5") (pintype "passive"))
      (node (ref "IC3") (pin "14") (pinfunction "D_14") (pintype "input"))
      (node (ref "R17") (pin "1") (pinfunction "1_1") (pintype "passive"))
    )
    (net (code "33") (name "Net-(IC3A-E)") (class "Default")
      (node (ref "CN4") (pin "6") (pinfunction "6_6") (pintype "passive"))
      (node (ref "IC3") (pin "3") (pinfunction "E_3") (pintype "input"))
      (node (ref "R18") (pin "1") (pinfunction "1_1") (pintype "passive"))
    )
    (net (code "34") (name "Net-(IC3A-F)") (class "Default")
      (node (ref "CN4") (pin "7") (pinfunction "7_7") (pintype "passive"))
      (node (ref "IC3") (pin "4") (pinfunction "F_4") (pintype "input"))
      (node (ref "R19") (pin "1") (pinfunction "1_1") (pintype "passive"))
    )
    (net (code "35") (name "Net-(IC3A-G)") (class "Default")
      (node (ref "CN4") (pin "8") (pinfunction "8_8") (pintype "passive"))
      (node (ref "IC3") (pin "5") (pinfunction "G_5") (pintype "input"))
      (node (ref "R20") (pin "1") (pinfunction "1_1") (pintype "passive"))
    )
    (net (code "36") (name "Net-(IC3A-H)") (class "Default")
      (node (ref "CN4") (pin "9") (pinfunction "9_9") (pintype "passive"))
      (node (ref "IC3") (pin "6") (pinfunction "H_6") (pintype "input"))
      (node (ref "R21") (pin "1") (pinfunction "1_1") (pintype "passive"))
    )
    (net (code "37") (name "Net-(IC3A-QH)") (class "Default")
      (node (ref "IC3") (pin "9") (pinfunction "QH_9") (pintype "output"))
      (node (ref "IC4") (pin "10") (pinfunction "SER_10") (pintype "input"))
    )
    (net (code "38") (name "Net-(IC4A-A)") (class "Default")
      (node (ref "CN5") (pin "2") (pinfunction "2_2") (pintype "passive"))
      (node (ref "IC4") (pin "11") (pinfunction "A_11") (pintype "input"))
      (node (ref "R6") (pin "1") (pinfunction "1_1") (pintype "passive"))
    )
    (net (code "39") (name "Net-(IC4A-B)") (class "Default")
      (node (ref "CN5") (pin "3") (pinfunction "3_3") (pintype "passive"))
      (node (ref "IC4") (pin "12") (pinfunction "B_12") (pintype "input"))
      (node (ref "R7") (pin "1") (pinfunction "1_1") (pintype "passive"))
    )
    (net (code "40") (name "Net-(IC4A-C)") (class "Default")
      (node (ref "CN5") (pin "4") (pinfunction "4_4") (pintype "passive"))
      (node (ref "IC4") (pin "13") (pinfunction "C_13") (pintype "input"))
      (node (ref "R8") (pin "1") (pinfunction "1_1") (pintype "passive"))
    )
    (net (code "41") (name "Net-(IC4A-D)") (class "Default")
      (node (ref "CN5") (pin "5") (pinfunction "5_5") (pintype "passive"))
      (node (ref "IC4") (pin "14") (pinfunction "D_14") (pintype "input"))
      (node (ref "R9") (pin "1") (pinfunction "1_1") (pintype "passive"))
    )
    (net (code "42") (name "Net-(IC4A-E)") (class "Default")
      (node (ref "CN5") (pin "6") (pinfunction "6_6") (pintype "passive"))
      (node (ref "IC4") (pin "3") (pinfunction "E_3") (pintype "input"))
      (node (ref "R10") (pin "1") (pinfunction "1_1") (pintype "passive"))
    )
    (net (code "43") (name "Net-(IC4A-F)") (class "Default")
      (node (ref "CN5") (pin "7") (pinfunction "7_7") (pintype "passive"))
      (node (ref "IC4") (pin "4") (pinfunction "F_4") (pintype "input"))
      (node (ref "R11") (pin "1") (pinfunction "1_1") (pintype "passive"))
    )
    (net (code "44") (name "Net-(IC4A-G)") (class "Default")
      (node (ref "CN5") (pin "8") (pinfunction "8_8") (pintype "passive"))
      (node (ref "IC4") (pin "5") (pinfunction "G_5") (pintype "input"))
      (node (ref "R12") (pin "1") (pinfunction "1_1") (pintype "passive"))
    )
    (net (code "45") (name "Net-(IC4A-H)") (class "Default")
      (node (ref "CN5") (pin "9") (pinfunction "9_9") (pintype "passive"))
      (node (ref "IC4") (pin "6") (pinfunction "H_6") (pintype "input"))
      (node (ref "R13") (pin "1") (pinfunction "1_1") (pintype "passive"))
    )
    (net (code "46") (name "Net-(IC4A-QH)") (class "Default")
      (node (ref "IC4") (pin "9") (pinfunction "QH_9") (pintype "output"))
      (node (ref "R4") (pin "1") (pinfunction "1_1") (pintype "passive"))
    )
    (net (code "47") (name "Net-(IC5A-CLK)") (class "Default")
      (node (ref "IC5") (pin "3") (pinfunction "CLK_3") (pintype "input"))
      (node (ref "R2") (pin "2") (pinfunction "2_2") (pintype "passive"))
    )
    (net (code "48") (name "Net-(IC5A-CLR)") (class "Default")
      (node (ref "IC5") (pin "1") (pinfunction "CLR_1") (pintype "input"))
      (node (ref "IC5") (pin "11") (pinfunction "CLK_11") (pintype "input"))
      (node (ref "R3") (pin "2") (pinfunction "2_2") (pintype "passive"))
    )
    (net (code "49") (name "Net-(IC5B-D)") (class "Default")
      (node (ref "IC5") (pin "12") (pinfunction "D_12") (pintype "input"))
      (node (ref "R1") (pin "2") (pinfunction "2_2") (pintype "passive"))
    )
    (net (code "50") (name "Net-(R6-Pad2)") (class "Default")
      (node (ref "R6") (pin "2") (pinfunction "2_2") (pintype "passive"))
      (node (ref "U$39") (pin "1") (pinfunction "1_1") (pintype "passive"))
    )
    (net (code "51") (name "Net-(R7-Pad2)") (class "Default")
      (node (ref "R7") (pin "2") (pinfunction "2_2") (pintype "passive"))
      (node (ref "U$38") (pin "1") (pinfunction "1_1") (pintype "passive"))
    )
    (net (code "52") (name "Net-(R8-Pad2)") (class "Default")
      (node (ref "R8") (pin "2") (pinfunction "2_2") (pintype "passive"))
      (node (ref "U$37") (pin "1") (pinfunction "1_1") (pintype "passive"))
    )
    (net (code "53") (name "Net-(R9-Pad2)") (class "Default")
      (node (ref "R9") (pin "2") (pinfunction "2_2") (pintype "passive"))
      (node (ref "U$36") (pin "1") (pinfunction "1_1") (pintype "passive"))
    )
    (net (code "54") (name "Net-(R10-Pad2)") (class "Default")
      (node (ref "R10") (pin "2") (pinfunction "2_2") (pintype "passive"))
      (node (ref "U$35") (pin "1") (pinfunction "1_1") (pintype "passive"))
    )
    (net (code "55") (name "Net-(R11-Pad2)") (class "Default")
      (node (ref "R11") (pin "2") (pinfunction "2_2") (pintype "passive"))
      (node (ref "U$34") (pin "1") (pinfunction "1_1") (pintype "passive"))
    )
    (net (code "56") (name "Net-(R12-Pad2)") (class "Default")
      (node (ref "R12") (pin "2") (pinfunction "2_2") (pintype "passive"))
      (node (ref "U$33") (pin "1") (pinfunction "1_1") (pintype "passive"))
    )
    (net (code "57") (name "Net-(R13-Pad2)") (class "Default")
      (node (ref "R13") (pin "2") (pinfunction "2_2") (pintype "passive"))
      (node (ref "U$32") (pin "1") (pinfunction "1_1") (pintype "passive"))
    )
    (net (code "58") (name "Net-(R14-Pad2)") (class "Default")
      (node (ref "R14") (pin "2") (pinfunction "2_2") (pintype "passive"))
      (node (ref "U$31") (pin "1") (pinfunction "1_1") (pintype "passive"))
    )
    (net (code "59") (name "Net-(R15-Pad2)") (class "Default")
      (node (ref "R15") (pin "2") (pinfunction "2_2") (pintype "passive"))
      (node (ref "U$30") (pin "1") (pinfunction "1_1") (pintype "passive"))
    )
    (net (code "60") (name "Net-(R16-Pad2)") (class "Default")
      (node (ref "R16") (pin "2") (pinfunction "2_2") (pintype "passive"))
      (node (ref "U$29") (pin "1") (pinfunction "1_1") (pintype "passive"))
    )
    (net (code "61") (name "Net-(R17-Pad2)") (class "Default")
      (node (ref "R17") (pin "2") (pinfunction "2_2") (pintype "passive"))
      (node (ref "U$28") (pin "1") (pinfunction "1_1") (pintype "passive"))
    )
    (net (code "62") (name "Net-(R18-Pad2)") (class "Default")
      (node (ref "R18") (pin "2") (pinfunction "2_2") (pintype "passive"))
      (node (ref "U$27") (pin "1") (pinfunction "1_1") (pintype "passive"))
    )
    (net (code "63") (name "Net-(R19-Pad2)") (class "Default")
      (node (ref "R19") (pin "2") (pinfunction "2_2") (pintype "passive"))
      (node (ref "U$26") (pin "1") (pinfunction "1_1") (pintype "passive"))
    )
    (net (code "64") (name "Net-(R20-Pad2)") (class "Default")
      (node (ref "R20") (pin "2") (pinfunction "2_2") (pintype "passive"))
      (node (ref "U$25") (pin "1") (pinfunction "1_1") (pintype "passive"))
    )
    (net (code "65") (name "Net-(R21-Pad2)") (class "Default")
      (node (ref "R21") (pin "2") (pinfunction "2_2") (pintype "passive"))
      (node (ref "U$24") (pin "1") (pinfunction "1_1") (pintype "passive"))
    )
    (net (code "66") (name "Net-(R22-Pad2)") (class "Default")
      (node (ref "R22") (pin "2") (pinfunction "2_2") (pintype "passive"))
      (node (ref "U$23") (pin "1") (pinfunction "1_1") (pintype "passive"))
    )
    (net (code "67") (name "Net-(R23-Pad2)") (class "Default")
      (node (ref "R23") (pin "2") (pinfunction "2_2") (pintype "passive"))
      (node (ref "U$22") (pin "1") (pinfunction "1_1") (pintype "passive"))
    )
    (net (code "68") (name "Net-(R24-Pad2)") (class "Default")
      (node (ref "R24") (pin "2") (pinfunction "2_2") (pintype "passive"))
      (node (ref "U$21") (pin "1") (pinfunction "1_1") (pintype "passive"))
    )
    (net (code "69") (name "Net-(R25-Pad2)") (class "Default")
      (node (ref "R25") (pin "2") (pinfunction "2_2") (pintype "passive"))
      (node (ref "U$20") (pin "1") (pinfunction "1_1") (pintype "passive"))
    )
    (net (code "70") (name "Net-(R26-Pad2)") (class "Default")
      (node (ref "R26") (pin "2") (pinfunction "2_2") (pintype "passive"))
      (node (ref "U$19") (pin "1") (pinfunction "1_1") (pintype "passive"))
    )
    (net (code "71") (name "Net-(R27-Pad2)") (class "Default")
      (node (ref "R27") (pin "2") (pinfunction "2_2") (pintype "passive"))
      (node (ref "U$18") (pin "1") (pinfunction "1_1") (pintype "passive"))
    )
    (net (code "72") (name "Net-(R28-Pad2)") (class "Default")
      (node (ref "R28") (pin "2") (pinfunction "2_2") (pintype "passive"))
      (node (ref "U$17") (pin "1") (pinfunction "1_1") (pintype "passive"))
    )
    (net (code "73") (name "Net-(R29-Pad2)") (class "Default")
      (node (ref "R29") (pin "2") (pinfunction "2_2") (pintype "passive"))
      (node (ref "U$16") (pin "1") (pinfunction "1_1") (pintype "passive"))
    )
    (net (code "74") (name "Net-(R30-Pad2)") (class "Default")
      (node (ref "R30") (pin "2") (pinfunction "2_2") (pintype "passive"))
      (node (ref "U$15") (pin "1") (pinfunction "1_1") (pintype "passive"))
    )
    (net (code "75") (name "Net-(R31-Pad2)") (class "Default")
      (node (ref "R31") (pin "2") (pinfunction "2_2") (pintype "passive"))
      (node (ref "U$14") (pin "1") (pinfunction "1_1") (pintype "passive"))
    )
    (net (code "76") (name "Net-(R32-Pad2)") (class "Default")
      (node (ref "R32") (pin "2") (pinfunction "2_2") (pintype "passive"))
      (node (ref "U$13") (pin "1") (pinfunction "1_1") (pintype "passive"))
    )
    (net (code "77") (name "Net-(R33-Pad2)") (class "Default")
      (node (ref "R33") (pin "2") (pinfunction "2_2") (pintype "passive"))
      (node (ref "U$12") (pin "1") (pinfunction "1_1") (pintype "passive"))
    )
    (net (code "78") (name "Net-(R34-Pad2)") (class "Default")
      (node (ref "R34") (pin "2") (pinfunction "2_2") (pintype "passive"))
      (node (ref "U$11") (pin "1") (pinfunction "1_1") (pintype "passive"))
    )
    (net (code "79") (name "Net-(R35-Pad2)") (class "Default")
      (node (ref "R35") (pin "2") (pinfunction "2_2") (pintype "passive"))
      (node (ref "U$10") (pin "1") (pinfunction "1_1") (pintype "passive"))
    )
    (net (code "80") (name "Net-(R36-Pad2)") (class "Default")
      (node (ref "R36") (pin "2") (pinfunction "2_2") (pintype "passive"))
      (node (ref "U$9") (pin "1") (pinfunction "1_1") (pintype "passive"))
    )
    (net (code "81") (name "Net-(R37-Pad2)") (class "Default")
      (node (ref "R37") (pin "2") (pinfunction "2_2") (pintype "passive"))
      (node (ref "U$8") (pin "1") (pinfunction "1_1") (pintype "passive"))
    )
    (net (code "82") (name "VCC") (class "Default")
      (node (ref "BB4") (pin "7") (pinfunction "7_7") (pintype "passive"))
    )
    (net (code "83") (name "unconnected-(IC1A-~{QH}-Pad7)") (class "Default")
      (node (ref "IC1") (pin "7") (pinfunction "~{QH}_7") (pintype "output"))
    )
    (net (code "84") (name "unconnected-(IC2A-~{QH}-Pad7)") (class "Default")
      (node (ref "IC2") (pin "7") (pinfunction "~{QH}_7") (pintype "output"))
    )
    (net (code "85") (name "unconnected-(IC3A-~{QH}-Pad7)") (class "Default")
      (node (ref "IC3") (pin "7") (pinfunction "~{QH}_7") (pintype "output"))
    )
    (net (code "86") (name "unconnected-(IC4A-~{QH}-Pad7)") (class "Default")
      (node (ref "IC4") (pin "7") (pinfunction "~{QH}_7") (pintype "output"))
    )
    (net (code "87") (name "unconnected-(IC5A-~{Q}-Pad6)") (class "Default")
      (node (ref "IC5") (pin "6") (pinfunction "~{Q}_6") (pintype "output"))
    )
    (net (code "88") (name "unconnected-(IC5B-~{Q}-Pad8)") (class "Default")
      (node (ref "IC5") (pin "8") (pinfunction "~{Q}_8") (pintype "output"))
    )
  )
)
